# other.net
KiCad netlist of a schematic drawn in Altium Designer
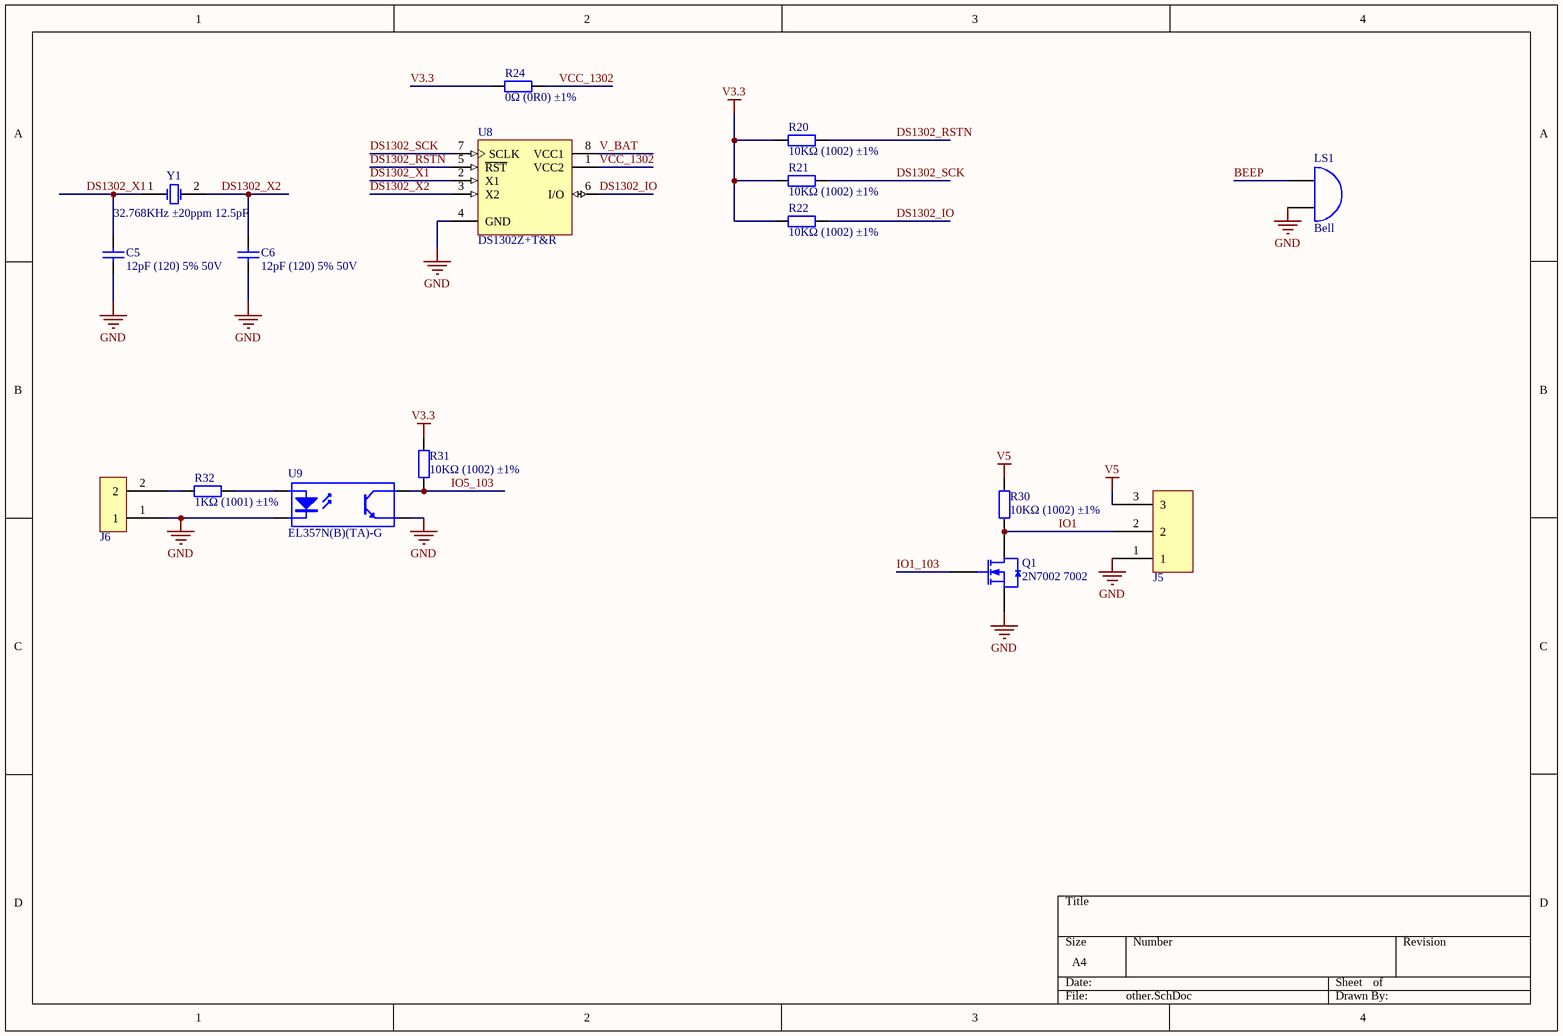
[diagram p0: other.SchDoc]

(export (version "E")
  (design (tool "Eeschema 10.0.6"))
  (components
    (comp (ref "C5")
      (value "12pF (120) 5% 50V")
      (footprint "0402_C")
      (description "贴片电容")
      (libsource (lib "Miscellaneous Devices LC") (part "0402 12pF (120) 5% 50V"))
    )
    (comp (ref "C6")
      (value "12pF (120) 5% 50V")
      (footprint "0402_C")
      (description "贴片电容")
      (libsource (lib "Miscellaneous Devices LC") (part "0402 12pF (120) 5% 50V"))
    )
    (comp (ref "J5") (value "KF301-3P") (footprint "KF301-3P") (libsource (lib "CHK-I") (part "KF301-3P")))
    (comp (ref "J6") (value "KF301-2P") (footprint "KF301-2P") (libsource (lib "CHK-I") (part "KF301-2P")))
    (comp (ref "LS1")
      (value "Bell")
      (footprint "PIN2")
      (description "Electrical Bell")
      (fields (field (name "PUBLISHER") "Altium Limited"))
      (libsource (lib "Miscellaneous Devices") (part "Bell"))
    )
    (comp (ref "Q1")
      (value "2N7002 7002")
      (footprint "SOT-23(SOT-23-3)")
      (description "MOS(场效应管)")
      (libsource (lib "Miscellaneous Devices LC") (part "2N7002 7002"))
    )
    (comp (ref "R20")
      (value "10KΩ (1002) ±1%")
      (footprint "0402_R")
      (description "贴片电阻")
      (libsource (lib "Miscellaneous Devices LC") (part "0402 10KΩ (1002) 1%"))
    )
    (comp (ref "R21")
      (value "10KΩ (1002) ±1%")
      (footprint "0402_R")
      (description "贴片电阻")
      (libsource (lib "Miscellaneous Devices LC") (part "0402 10KΩ (1002) 1%"))
    )
    (comp (ref "R22")
      (value "10KΩ (1002) ±1%")
      (footprint "0402_R")
      (description "贴片电阻")
      (libsource (lib "Miscellaneous Devices LC") (part "0402 10KΩ (1002) 1%"))
    )
    (comp (ref "R24")
      (value "0Ω (0R0) ±1%")
      (footprint "1206_R")
      (description "贴片电阻")
      (libsource (lib "Miscellaneous Devices LC") (part "1206 0Ω (0R0) 1%"))
    )
    (comp (ref "R30")
      (value "10KΩ (1002) ±1%")
      (footprint "1206_R")
      (description "贴片电阻")
      (libsource (lib "Miscellaneous Devices LC") (part "1206 10KΩ (1002) 1%"))
    )
    (comp (ref "R31")
      (value "10KΩ (1002) ±1%")
      (footprint "1206_R")
      (description "贴片电阻")
      (libsource (lib "Miscellaneous Devices LC") (part "1206 10KΩ (1002) 1%"))
    )
    (comp (ref "R32")
      (value "1KΩ (1001) ±1%")
      (footprint "1206_R")
      (description "贴片电阻")
      (libsource (lib "Miscellaneous Devices LC") (part "1206 1KΩ (1001) 1%"))
    )
    (comp (ref "U8")
      (value "DS1302Z+T&R")
      (footprint "SOIC-8_150mil")
      (description "实时时钟")
      (libsource (lib "Miscellaneous Devices LC") (part "DS1302Z+T&R_[C8959]"))
    )
    (comp (ref "U9")
      (value "EL357N(B)(TA)-G")
      (footprint "SOP-4_P2.54")
      (description "贴片光耦")
      (libsource (lib "Miscellaneous Devices LC") (part "EL357N(B)(TA)-G_[C6649]"))
    )
    (comp (ref "Y1")
      (value "32.768KHz ±20ppm 12.5pF")
      (footprint "SMD-3215_2P FC - 135")
      (description "贴片晶振")
      (libsource (lib "Miscellaneous Devices LC") (part "SMD-3215_2P 32.768KHz 20ppm 12.5pF"))
    )
  )
  (nets
    (net (code "1") (name "/BEEP") (class "Default")
      (node (ref "LS1") (pin "1") (pinfunction "A_1") (pintype "passive"))
    )
    (net (code "2") (name "/DS1302_IO") (class "Default")
      (node (ref "R22") (pin "2") (pinfunction "2_2") (pintype "passive"))
      (node (ref "U8") (pin "6") (pinfunction "I/O_6") (pintype "bidirectional"))
    )
    (net (code "3") (name "/DS1302_RSTN") (class "Default")
      (node (ref "R20") (pin "2") (pinfunction "2_2") (pintype "passive"))
      (node (ref "U8") (pin "5") (pinfunction "~{RST}_5") (pintype "input"))
    )
    (net (code "4") (name "/DS1302_SCK") (class "Default")
      (node (ref "R21") (pin "2") (pinfunction "2_2") (pintype "passive"))
      (node (ref "U8") (pin "7") (pinfunction "SCLK_7") (pintype "input"))
    )
    (net (code "5") (name "/DS1302_X1") (class "Default")
      (node (ref "C5") (pin "2") (pinfunction "2_2") (pintype "passive"))
      (node (ref "U8") (pin "2") (pinfunction "X1_2") (pintype "input"))
      (node (ref "Y1") (pin "1") (pinfunction "OSC1_1") (pintype "passive"))
    )
    (net (code "6") (name "/DS1302_X2") (class "Default")
      (node (ref "C6") (pin "2") (pinfunction "2_2") (pintype "passive"))
      (node (ref "U8") (pin "3") (pinfunction "X2_3") (pintype "input"))
      (node (ref "Y1") (pin "2") (pinfunction "OSC2_2") (pintype "passive"))
    )
    (net (code "7") (name "/IO1") (class "Default")
      (node (ref "J5") (pin "2") (pinfunction "2_2") (pintype "passive"))
      (node (ref "Q1") (pin "3") (pinfunction "D_3") (pintype "passive"))
      (node (ref "R30") (pin "1") (pinfunction "1_1") (pintype "passive"))
    )
    (net (code "8") (name "/IO1_103") (class "Default")
      (node (ref "Q1") (pin "1") (pinfunction "G_1") (pintype "passive"))
    )
    (net (code "9") (name "/IO5_103") (class "Default")
      (node (ref "R31") (pin "1") (pinfunction "1_1") (pintype "passive"))
      (node (ref "U9") (pin "4") (pinfunction "C_4") (pintype "passive"))
    )
    (net (code "10") (name "/VCC_1302") (class "Default")
      (node (ref "R24") (pin "2") (pinfunction "2_2") (pintype "passive"))
      (node (ref "U8") (pin "1") (pinfunction "VCC2_1") (pintype "power_in"))
    )
    (net (code "11") (name "/V_BAT") (class "Default")
      (node (ref "U8") (pin "8") (pinfunction "VCC1_8") (pintype "power_in"))
    )
    (net (code "12") (name "GND") (class "Default")
      (node (ref "C5") (pin "1") (pinfunction "1_1") (pintype "passive"))
      (node (ref "C6") (pin "1") (pinfunction "1_1") (pintype "passive"))
      (node (ref "J5") (pin "1") (pinfunction "1_1") (pintype "passive"))
      (node (ref "J6") (pin "1") (pinfunction "1_1") (pintype "passive"))
      (node (ref "LS1") (pin "2") (pinfunction "B_2") (pintype "passive"))
      (node (ref "Q1") (pin "2") (pinfunction "S_2") (pintype "passive"))
      (node (ref "U8") (pin "4") (pinfunction "GND_4") (pintype "power_in"))
      (node (ref "U9") (pin "2") (pinfunction "K_2") (pintype "passive"))
      (node (ref "U9") (pin "3") (pinfunction "E_3") (pintype "passive"))
    )
    (net (code "13") (name "Net-(J6-Pad2)") (class "Default")
      (node (ref "J6") (pin "2") (pinfunction "2_2") (pintype "passive"))
      (node (ref "R32") (pin "1") (pinfunction "1_1") (pintype "passive"))
    )
    (net (code "14") (name "Net-(U9-A)") (class "Default")
      (node (ref "R32") (pin "2") (pinfunction "2_2") (pintype "passive"))
      (node (ref "U9") (pin "1") (pinfunction "A_1") (pintype "passive"))
    )
    (net (code "15") (name "V3.3") (class "Default")
      (node (ref "R20") (pin "1") (pinfunction "1_1") (pintype "passive"))
      (node (ref "R21") (pin "1") (pinfunction "1_1") (pintype "passive"))
      (node (ref "R22") (pin "1") (pinfunction "1_1") (pintype "passive"))
      (node (ref "R24") (pin "1") (pinfunction "1_1") (pintype "passive"))
      (node (ref "R31") (pin "2") (pinfunction "2_2") (pintype "passive"))
    )
    (net (code "16") (name "V5") (class "Default")
      (node (ref "J5") (pin "3") (pinfunction "3_3") (pintype "passive"))
      (node (ref "R30") (pin "2") (pinfunction "2_2") (pintype "passive"))
    )
  )
)
